# Nixie2nd_ver1.net
KiCad netlist of a schematic drawn in EAGLE
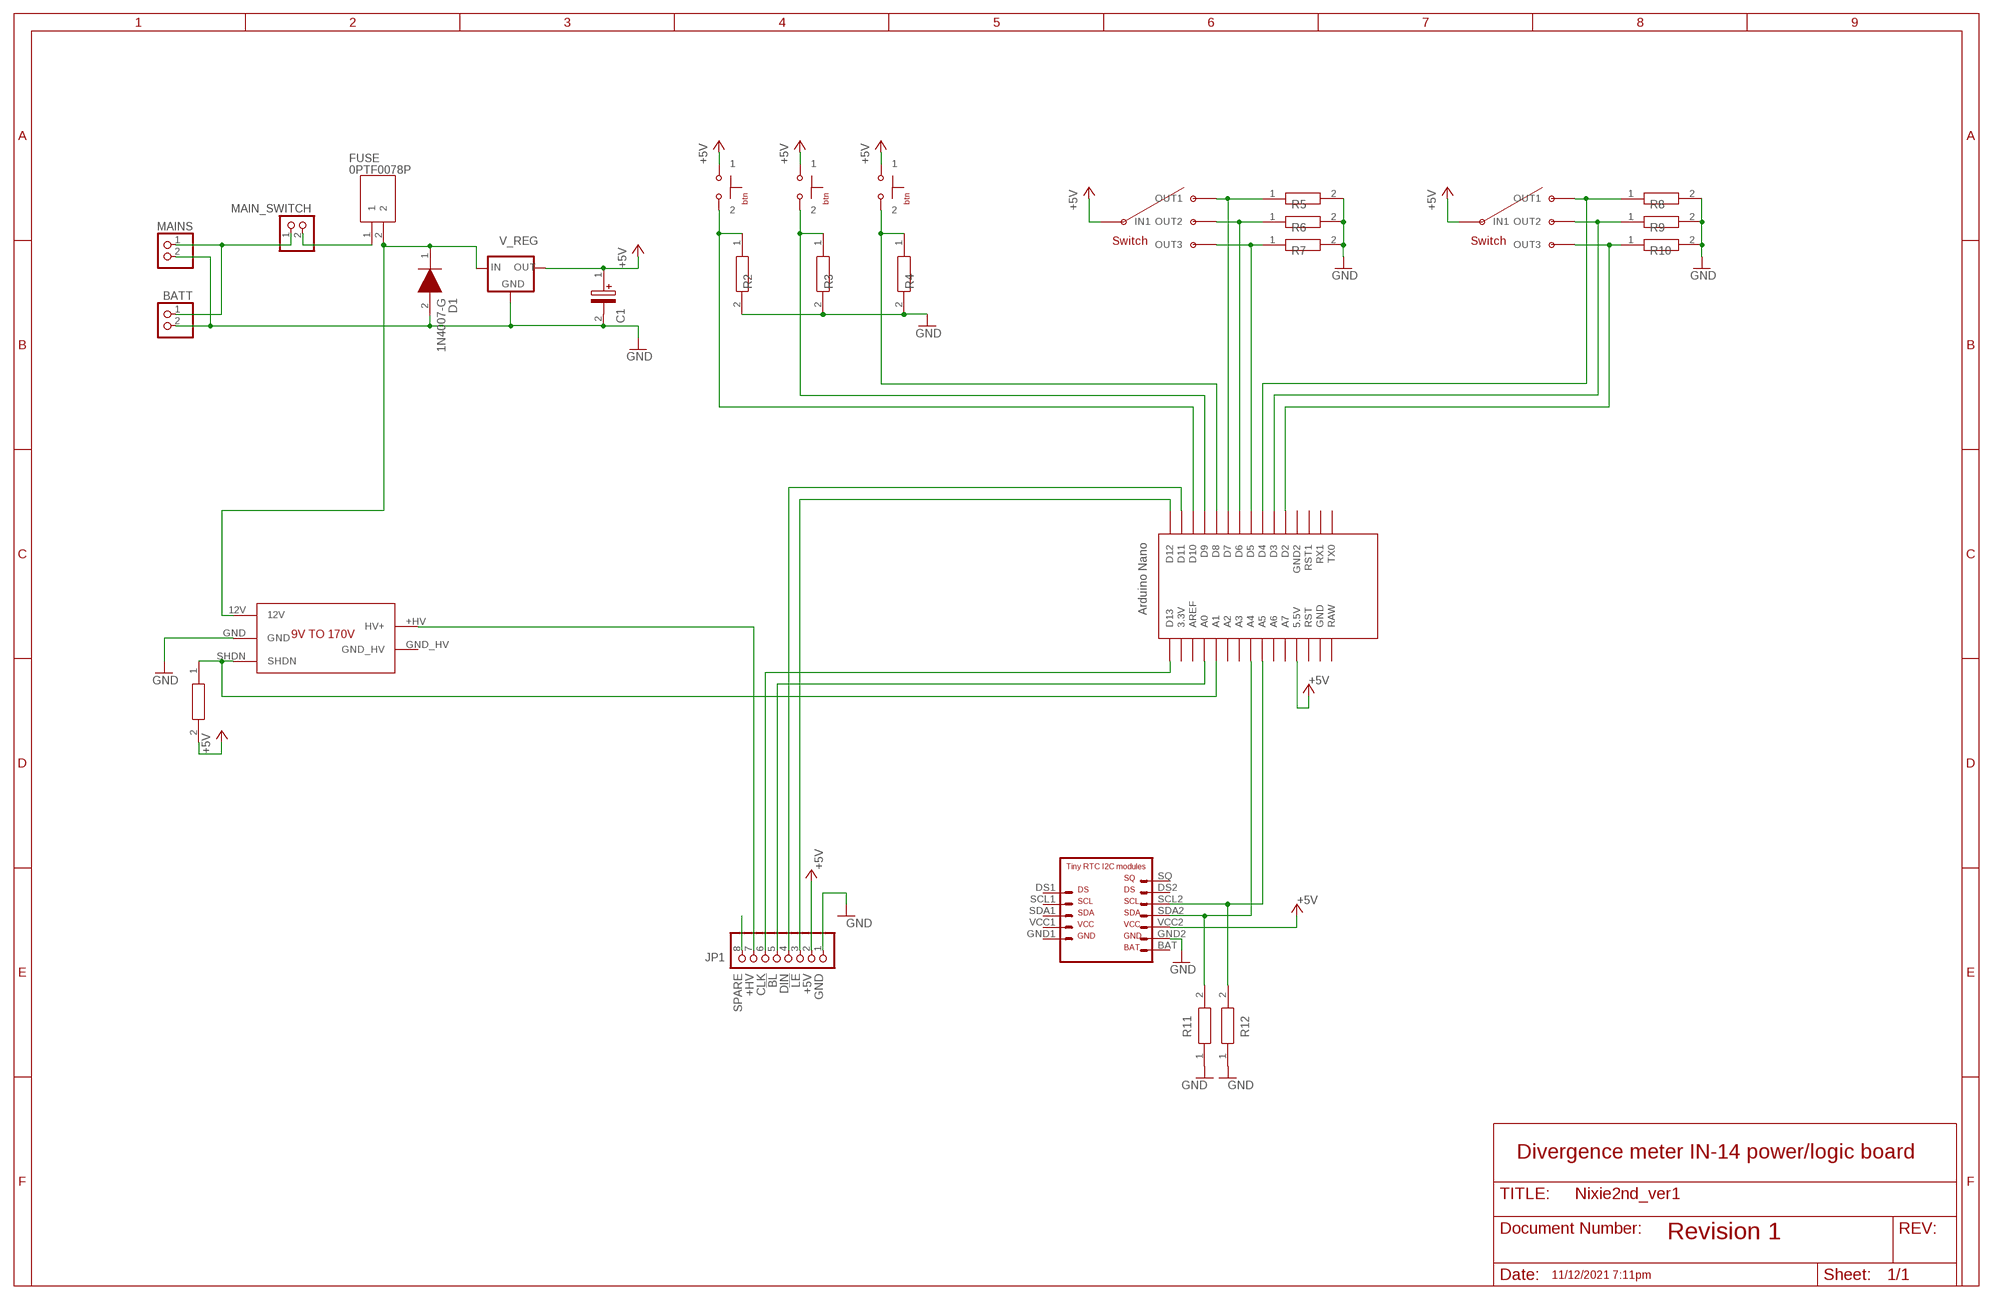
[diagram p0: schematic, sheet 1]

(export (version "E")
  (design (tool "Eeschema 10.0.6"))
  (components
    (comp (ref "BATT")
      (value "PINHD-1X2")
      (footprint "eagle-import:1X02")
      (libsource (lib "eagle-import") (part "PINHD-1X2"))
    )
    (comp (ref "BTN_1")
      (value "PUSH_BTN")
      (footprint "eagle-import:PUSH_BTN")
      (libsource (lib "eagle-import") (part "PUSH_BTN"))
    )
    (comp (ref "BTN_2")
      (value "PUSH_BTN")
      (footprint "eagle-import:PUSH_BTN")
      (libsource (lib "eagle-import") (part "PUSH_BTN"))
    )
    (comp (ref "BTN_3")
      (value "PUSH_BTN")
      (footprint "eagle-import:PUSH_BTN")
      (libsource (lib "eagle-import") (part "PUSH_BTN"))
    )
    (comp (ref "C1")
      (value "ESMG250ELL330ME11D")
      (footprint "eagle-import:CAPPRD275W60D825H1300")
      (fields (field (name "MOUSER_PART_NUMBER") "661-ESMG250L330ME11D"))
      (libsource (lib "eagle-import") (part "ESMG250ELL330ME11D"))
    )
    (comp (ref "D1")
      (value "1N4007-G")
      (footprint "eagle-import:DIOAD1410W90L470D235")
      (fields (field (name "MOUSER_PART_NUMBER") "750-1N4007-G"))
      (libsource (lib "eagle-import") (part "1N4007-G"))
    )
    (comp (ref "FUSE")
      (value "0PTF0078P")
      (footprint "eagle-import:0PTF0078P")
      (fields (field (name "MOUSER_PART_NUMBER") "576-0PTF0078P"))
      (libsource (lib "eagle-import") (part "0PTF0078P"))
    )
    (comp (ref "JP1")
      (value "PINHD-1X8")
      (footprint "eagle-import:1X08")
      (libsource (lib "eagle-import") (part "PINHD-1X8"))
    )
    (comp (ref "MAINS")
      (value "PINHD-1X2")
      (footprint "eagle-import:1X02")
      (libsource (lib "eagle-import") (part "PINHD-1X2"))
    )
    (comp (ref "MAIN_SWITCH")
      (value "PINHD-1X2")
      (footprint "eagle-import:1X02")
      (libsource (lib "eagle-import") (part "PINHD-1X2"))
    )
    (comp (ref "R1")
      (value "CR0805-FX-3303ELF")
      (footprint "eagle-import:RESC2012X60N")
      (fields (field (name "MOUSER_PART_NUMBER") "652-CR0805FX-3303ELF"))
      (libsource (lib "eagle-import") (part "CR0805-FX-3303ELF"))
    )
    (comp (ref "R2")
      (value "CR0805-FX-3303ELF")
      (footprint "eagle-import:RESC2012X60N")
      (fields (field (name "MOUSER_PART_NUMBER") "652-CR0805FX-3303ELF"))
      (libsource (lib "eagle-import") (part "CR0805-FX-3303ELF"))
    )
    (comp (ref "R3")
      (value "CR0805-FX-3303ELF")
      (footprint "eagle-import:RESC2012X60N")
      (fields (field (name "MOUSER_PART_NUMBER") "652-CR0805FX-3303ELF"))
      (libsource (lib "eagle-import") (part "CR0805-FX-3303ELF"))
    )
    (comp (ref "R4")
      (value "CR0805-FX-3303ELF")
      (footprint "eagle-import:RESC2012X60N")
      (fields (field (name "MOUSER_PART_NUMBER") "652-CR0805FX-3303ELF"))
      (libsource (lib "eagle-import") (part "CR0805-FX-3303ELF"))
    )
    (comp (ref "R5")
      (value "CR0805-FX-3303ELF")
      (footprint "eagle-import:RESC2012X60N")
      (fields (field (name "MOUSER_PART_NUMBER") "652-CR0805FX-3303ELF"))
      (libsource (lib "eagle-import") (part "CR0805-FX-3303ELF"))
    )
    (comp (ref "R6")
      (value "CR0805-FX-3303ELF")
      (footprint "eagle-import:RESC2012X60N")
      (fields (field (name "MOUSER_PART_NUMBER") "652-CR0805FX-3303ELF"))
      (libsource (lib "eagle-import") (part "CR0805-FX-3303ELF"))
    )
    (comp (ref "R7")
      (value "CR0805-FX-3303ELF")
      (footprint "eagle-import:RESC2012X60N")
      (fields (field (name "MOUSER_PART_NUMBER") "652-CR0805FX-3303ELF"))
      (libsource (lib "eagle-import") (part "CR0805-FX-3303ELF"))
    )
    (comp (ref "R8")
      (value "CR0805-FX-3303ELF")
      (footprint "eagle-import:RESC2012X60N")
      (fields (field (name "MOUSER_PART_NUMBER") "652-CR0805FX-3303ELF"))
      (libsource (lib "eagle-import") (part "CR0805-FX-3303ELF"))
    )
    (comp (ref "R9")
      (value "CR0805-FX-3303ELF")
      (footprint "eagle-import:RESC2012X60N")
      (fields (field (name "MOUSER_PART_NUMBER") "652-CR0805FX-3303ELF"))
      (libsource (lib "eagle-import") (part "CR0805-FX-3303ELF"))
    )
    (comp (ref "R10")
      (value "CR0805-FX-3303ELF")
      (footprint "eagle-import:RESC2012X60N")
      (fields (field (name "MOUSER_PART_NUMBER") "652-CR0805FX-3303ELF"))
      (libsource (lib "eagle-import") (part "CR0805-FX-3303ELF"))
    )
    (comp (ref "R11")
      (value "CR0805-FX-3303ELF")
      (footprint "eagle-import:RESC2012X60N")
      (fields (field (name "MOUSER_PART_NUMBER") "652-CR0805FX-3303ELF"))
      (libsource (lib "eagle-import") (part "CR0805-FX-3303ELF"))
    )
    (comp (ref "R12")
      (value "CR0805-FX-3303ELF")
      (footprint "eagle-import:RESC2012X60N")
      (fields (field (name "MOUSER_PART_NUMBER") "652-CR0805FX-3303ELF"))
      (libsource (lib "eagle-import") (part "CR0805-FX-3303ELF"))
    )
    (comp (ref "SWITCH_1")
      (value "3WAY_SWITCH")
      (footprint "eagle-import:3WAY_SWITCH")
      (libsource (lib "eagle-import") (part "3WAY_SWITCH"))
    )
    (comp (ref "SWITCH_2")
      (value "3WAY_SWITCH")
      (footprint "eagle-import:3WAY_SWITCH")
      (libsource (lib "eagle-import") (part "3WAY_SWITCH"))
    )
    (comp (ref "U$1")
      (value "NANO")
      (footprint "eagle-import:NANO")
      (libsource (lib "eagle-import") (part "NANO"))
    )
    (comp (ref "U$2")
      (value "VOLTAGE_9TO170VOLT_9TO170")
      (footprint "eagle-import:VOLTAGE_9TO170")
      (libsource (lib "eagle-import") (part "VOLTAGE_9TO170VOLT_9TO170"))
    )
    (comp (ref "U$3")
      (value "RTC")
      (footprint "eagle-import:RTC")
      (libsource (lib "eagle-import") (part "RTC"))
    )
    (comp (ref "V_REG")
      (value "78XXS")
      (footprint "eagle-import:78XXS")
      (libsource (lib "eagle-import") (part "78XXS"))
    )
  )
  (nets
    (net (code "1") (name "+5V") (class "Default")
      (node (ref "BTN_1") (pin "1") (pinfunction "1_1") (pintype "bidirectional"))
      (node (ref "BTN_2") (pin "1") (pinfunction "1_1") (pintype "bidirectional"))
      (node (ref "BTN_3") (pin "1") (pinfunction "1_1") (pintype "bidirectional"))
      (node (ref "C1") (pin "1") (pinfunction "+_1") (pintype "bidirectional"))
      (node (ref "JP1") (pin "2") (pinfunction "2_2") (pintype "passive"))
      (node (ref "R1") (pin "2") (pinfunction "2_2") (pintype "bidirectional"))
      (node (ref "SWITCH_1") (pin "IN1") (pinfunction "IN1_IN1") (pintype "bidirectional"))
      (node (ref "SWITCH_2") (pin "IN1") (pinfunction "IN1_IN1") (pintype "bidirectional"))
      (node (ref "U$1") (pin "5V") (pinfunction "5.5V_5V") (pintype "bidirectional"))
      (node (ref "U$3") (pin "VCC2") (pinfunction "VCC2_VCC2") (pintype "passive"))
      (node (ref "V_REG") (pin "OUT") (pinfunction "OUT_OUT") (pintype "passive"))
    )
    (net (code "2") (name "/+HV") (class "Default")
      (node (ref "JP1") (pin "7") (pinfunction "7_7") (pintype "passive"))
      (node (ref "U$2") (pin "+HV") (pinfunction "HV+_+HV") (pintype "bidirectional"))
    )
    (net (code "3") (name "/CLK") (class "Default")
      (node (ref "JP1") (pin "6") (pinfunction "6_6") (pintype "passive"))
      (node (ref "U$1") (pin "D13") (pinfunction "D13_D13") (pintype "bidirectional"))
    )
    (net (code "4") (name "/DIN") (class "Default")
      (node (ref "JP1") (pin "4") (pinfunction "4_4") (pintype "passive"))
      (node (ref "U$1") (pin "D11") (pinfunction "D11_D11") (pintype "bidirectional"))
    )
    (net (code "5") (name "/SPARE") (class "Default")
      (node (ref "JP1") (pin "8") (pinfunction "8_8") (pintype "passive"))
    )
    (net (code "6") (name "/~{BL}") (class "Default")
      (node (ref "JP1") (pin "5") (pinfunction "5_5") (pintype "passive"))
      (node (ref "U$1") (pin "A0") (pinfunction "A0_A0") (pintype "bidirectional"))
    )
    (net (code "7") (name "/~{LE}") (class "Default")
      (node (ref "JP1") (pin "3") (pinfunction "3_3") (pintype "passive"))
      (node (ref "U$1") (pin "D12") (pinfunction "D12_D12") (pintype "bidirectional"))
    )
    (net (code "8") (name "GND") (class "Default")
      (node (ref "BATT") (pin "2") (pinfunction "2_2") (pintype "passive"))
      (node (ref "C1") (pin "2") (pinfunction "-_2") (pintype "bidirectional"))
      (node (ref "D1") (pin "2") (pinfunction "A_2") (pintype "bidirectional"))
      (node (ref "JP1") (pin "1") (pinfunction "1_1") (pintype "passive"))
      (node (ref "MAINS") (pin "2") (pinfunction "2_2") (pintype "passive"))
      (node (ref "R10") (pin "2") (pinfunction "2_2") (pintype "bidirectional"))
      (node (ref "R11") (pin "1") (pinfunction "1_1") (pintype "bidirectional"))
      (node (ref "R12") (pin "1") (pinfunction "1_1") (pintype "bidirectional"))
      (node (ref "R2") (pin "2") (pinfunction "2_2") (pintype "bidirectional"))
      (node (ref "R3") (pin "2") (pinfunction "2_2") (pintype "bidirectional"))
      (node (ref "R4") (pin "2") (pinfunction "2_2") (pintype "bidirectional"))
      (node (ref "R5") (pin "2") (pinfunction "2_2") (pintype "bidirectional"))
      (node (ref "R6") (pin "2") (pinfunction "2_2") (pintype "bidirectional"))
      (node (ref "R7") (pin "2") (pinfunction "2_2") (pintype "bidirectional"))
      (node (ref "R8") (pin "2") (pinfunction "2_2") (pintype "bidirectional"))
      (node (ref "R9") (pin "2") (pinfunction "2_2") (pintype "bidirectional"))
      (node (ref "U$2") (pin "GND") (pinfunction "GND_GND") (pintype "bidirectional"))
      (node (ref "U$3") (pin "GND2") (pinfunction "GND2_GND2") (pintype "passive"))
      (node (ref "V_REG") (pin "GND") (pinfunction "GND_GND") (pintype "input"))
    )
    (net (code "9") (name "Net-(BATT-Pad1)") (class "Default")
      (node (ref "BATT") (pin "1") (pinfunction "1_1") (pintype "passive"))
      (node (ref "MAINS") (pin "1") (pinfunction "1_1") (pintype "passive"))
      (node (ref "MAIN_SWITCH") (pin "1") (pinfunction "1_1") (pintype "passive"))
    )
    (net (code "10") (name "Net-(BTN_1-Pad2)") (class "Default")
      (node (ref "BTN_1") (pin "2") (pinfunction "2_2") (pintype "bidirectional"))
      (node (ref "R2") (pin "1") (pinfunction "1_1") (pintype "bidirectional"))
      (node (ref "U$1") (pin "D10") (pinfunction "D10_D10") (pintype "bidirectional"))
    )
    (net (code "11") (name "Net-(BTN_2-Pad2)") (class "Default")
      (node (ref "BTN_2") (pin "2") (pinfunction "2_2") (pintype "bidirectional"))
      (node (ref "R3") (pin "1") (pinfunction "1_1") (pintype "bidirectional"))
      (node (ref "U$1") (pin "D9") (pinfunction "D9_D9") (pintype "bidirectional"))
    )
    (net (code "12") (name "Net-(BTN_3-Pad2)") (class "Default")
      (node (ref "BTN_3") (pin "2") (pinfunction "2_2") (pintype "bidirectional"))
      (node (ref "R4") (pin "1") (pinfunction "1_1") (pintype "bidirectional"))
      (node (ref "U$1") (pin "D8") (pinfunction "D8_D8") (pintype "bidirectional"))
    )
    (net (code "13") (name "Net-(D1-K)") (class "Default")
      (node (ref "D1") (pin "1") (pinfunction "K_1") (pintype "bidirectional"))
      (node (ref "FUSE") (pin "2") (pinfunction "2_2") (pintype "bidirectional"))
      (node (ref "U$2") (pin "12V") (pinfunction "12V_12V") (pintype "bidirectional"))
      (node (ref "V_REG") (pin "IN") (pinfunction "IN_IN") (pintype "input"))
    )
    (net (code "14") (name "Net-(FUSE-Pad1)") (class "Default")
      (node (ref "FUSE") (pin "1") (pinfunction "1_1") (pintype "bidirectional"))
      (node (ref "MAIN_SWITCH") (pin "2") (pinfunction "2_2") (pintype "passive"))
    )
    (net (code "15") (name "Net-(R1-Pad1)") (class "Default")
      (node (ref "R1") (pin "1") (pinfunction "1_1") (pintype "bidirectional"))
      (node (ref "U$1") (pin "A1") (pinfunction "A1_A1") (pintype "bidirectional"))
      (node (ref "U$2") (pin "SHDN") (pinfunction "SHDN_SHDN") (pintype "bidirectional"))
    )
    (net (code "16") (name "Net-(R5-Pad1)") (class "Default")
      (node (ref "R5") (pin "1") (pinfunction "1_1") (pintype "bidirectional"))
      (node (ref "SWITCH_1") (pin "OUT1") (pinfunction "OUT1_OUT1") (pintype "bidirectional"))
      (node (ref "U$1") (pin "D7") (pinfunction "D7_D7") (pintype "bidirectional"))
    )
    (net (code "17") (name "Net-(R6-Pad1)") (class "Default")
      (node (ref "R6") (pin "1") (pinfunction "1_1") (pintype "bidirectional"))
      (node (ref "SWITCH_1") (pin "OUT2") (pinfunction "OUT2_OUT2") (pintype "bidirectional"))
      (node (ref "U$1") (pin "D6") (pinfunction "D6_D6") (pintype "bidirectional"))
    )
    (net (code "18") (name "Net-(R8-Pad1)") (class "Default")
      (node (ref "R8") (pin "1") (pinfunction "1_1") (pintype "bidirectional"))
      (node (ref "SWITCH_2") (pin "OUT1") (pinfunction "OUT1_OUT1") (pintype "bidirectional"))
      (node (ref "U$1") (pin "D4") (pinfunction "D4_D4") (pintype "bidirectional"))
    )
    (net (code "19") (name "Net-(R9-Pad1)") (class "Default")
      (node (ref "R9") (pin "1") (pinfunction "1_1") (pintype "bidirectional"))
      (node (ref "SWITCH_2") (pin "OUT2") (pinfunction "OUT2_OUT2") (pintype "bidirectional"))
      (node (ref "U$1") (pin "D3") (pinfunction "D3_D3") (pintype "bidirectional"))
    )
    (net (code "20") (name "Net-(R11-Pad2)") (class "Default")
      (node (ref "R11") (pin "2") (pinfunction "2_2") (pintype "bidirectional"))
      (node (ref "U$1") (pin "A4") (pinfunction "A4_A4") (pintype "bidirectional"))
      (node (ref "U$3") (pin "SDA2") (pinfunction "SDA2_SDA2") (pintype "passive"))
    )
    (net (code "21") (name "Net-(R12-Pad2)") (class "Default")
      (node (ref "R12") (pin "2") (pinfunction "2_2") (pintype "bidirectional"))
      (node (ref "U$1") (pin "A5") (pinfunction "A5_A5") (pintype "bidirectional"))
      (node (ref "U$3") (pin "SCL2") (pinfunction "SCL2_SCL2") (pintype "passive"))
    )
    (net (code "22") (name "Net-(SWITCH_1-OUT3)") (class "Default")
      (node (ref "R7") (pin "1") (pinfunction "1_1") (pintype "bidirectional"))
      (node (ref "SWITCH_1") (pin "OU3") (pinfunction "OUT3_OU3") (pintype "bidirectional"))
      (node (ref "U$1") (pin "D5") (pinfunction "D5_D5") (pintype "bidirectional"))
    )
    (net (code "23") (name "Net-(SWITCH_2-OUT3)") (class "Default")
      (node (ref "R10") (pin "1") (pinfunction "1_1") (pintype "bidirectional"))
      (node (ref "SWITCH_2") (pin "OU3") (pinfunction "OUT3_OU3") (pintype "bidirectional"))
      (node (ref "U$1") (pin "D2") (pinfunction "D2_D2") (pintype "bidirectional"))
    )
    (net (code "24") (name "unconnected-(U$1-GND2-PadGND1)") (class "Default")
      (node (ref "U$1") (pin "GND1") (pinfunction "GND2_GND1") (pintype "bidirectional"))
    )
    (net (code "25") (name "unconnected-(U$1-Pad3.3V)") (class "Default")
      (node (ref "U$1") (pin "3.3V") (pinfunction "3.3V_3.3V") (pintype "bidirectional"))
    )
    (net (code "26") (name "unconnected-(U$1-PadA2)") (class "Default")
      (node (ref "U$1") (pin "A2") (pinfunction "A2_A2") (pintype "bidirectional"))
    )
    (net (code "27") (name "unconnected-(U$1-PadA3)") (class "Default")
      (node (ref "U$1") (pin "A3") (pinfunction "A3_A3") (pintype "bidirectional"))
    )
    (net (code "28") (name "unconnected-(U$1-PadA6)") (class "Default")
      (node (ref "U$1") (pin "A6") (pinfunction "A6_A6") (pintype "bidirectional"))
    )
    (net (code "29") (name "unconnected-(U$1-PadA7)") (class "Default")
      (node (ref "U$1") (pin "A7") (pinfunction "A7_A7") (pintype "bidirectional"))
    )
    (net (code "30") (name "unconnected-(U$1-PadAREF)") (class "Default")
      (node (ref "U$1") (pin "AREF") (pinfunction "AREF_AREF") (pintype "bidirectional"))
    )
    (net (code "31") (name "unconnected-(U$1-PadGND)") (class "Default")
      (node (ref "U$1") (pin "GND") (pinfunction "GND_GND") (pintype "bidirectional"))
    )
    (net (code "32") (name "unconnected-(U$1-PadRAW)") (class "Default")
      (node (ref "U$1") (pin "RAW") (pinfunction "RAW_RAW") (pintype "bidirectional"))
    )
    (net (code "33") (name "unconnected-(U$1-PadRST)") (class "Default")
      (node (ref "U$1") (pin "RST") (pinfunction "RST_RST") (pintype "bidirectional"))
    )
    (net (code "34") (name "unconnected-(U$1-PadRST1)") (class "Default")
      (node (ref "U$1") (pin "RST1") (pinfunction "RST1_RST1") (pintype "bidirectional"))
    )
    (net (code "35") (name "unconnected-(U$1-PadRX1)") (class "Default")
      (node (ref "U$1") (pin "RX1") (pinfunction "RX1_RX1") (pintype "bidirectional"))
    )
    (net (code "36") (name "unconnected-(U$1-PadTX0)") (class "Default")
      (node (ref "U$1") (pin "TX0") (pinfunction "TX0_TX0") (pintype "bidirectional"))
    )
    (net (code "37") (name "unconnected-(U$2-PadGND_HV)") (class "Default")
      (node (ref "U$2") (pin "GND_HV") (pinfunction "GND_HV_GND_HV") (pintype "bidirectional"))
    )
    (net (code "38") (name "unconnected-(U$3-PadBAT)") (class "Default")
      (node (ref "U$3") (pin "BAT") (pinfunction "BAT_BAT") (pintype "passive"))
    )
    (net (code "39") (name "unconnected-(U$3-PadDS1)") (class "Default")
      (node (ref "U$3") (pin "DS1") (pinfunction "DS1_DS1") (pintype "passive"))
    )
    (net (code "40") (name "unconnected-(U$3-PadDS2)") (class "Default")
      (node (ref "U$3") (pin "DS2") (pinfunction "DS2_DS2") (pintype "passive"))
    )
    (net (code "41") (name "unconnected-(U$3-PadGND1)") (class "Default")
      (node (ref "U$3") (pin "GND1") (pinfunction "GND1_GND1") (pintype "passive"))
    )
    (net (code "42") (name "unconnected-(U$3-PadSCL1)") (class "Default")
      (node (ref "U$3") (pin "SCL1") (pinfunction "SCL1_SCL1") (pintype "passive"))
    )
    (net (code "43") (name "unconnected-(U$3-PadSDA1)") (class "Default")
      (node (ref "U$3") (pin "SDA1") (pinfunction "SDA1_SDA1") (pintype "passive"))
    )
    (net (code "44") (name "unconnected-(U$3-PadSQ)") (class "Default")
      (node (ref "U$3") (pin "SQ") (pinfunction "SQ_SQ") (pintype "passive"))
    )
    (net (code "45") (name "unconnected-(U$3-PadVCC1)") (class "Default")
      (node (ref "U$3") (pin "VCC1") (pinfunction "VCC1_VCC1") (pintype "passive"))
    )
  )
)
